# DISPLAY.net
KiCad netlist of a schematic drawn in EAGLE
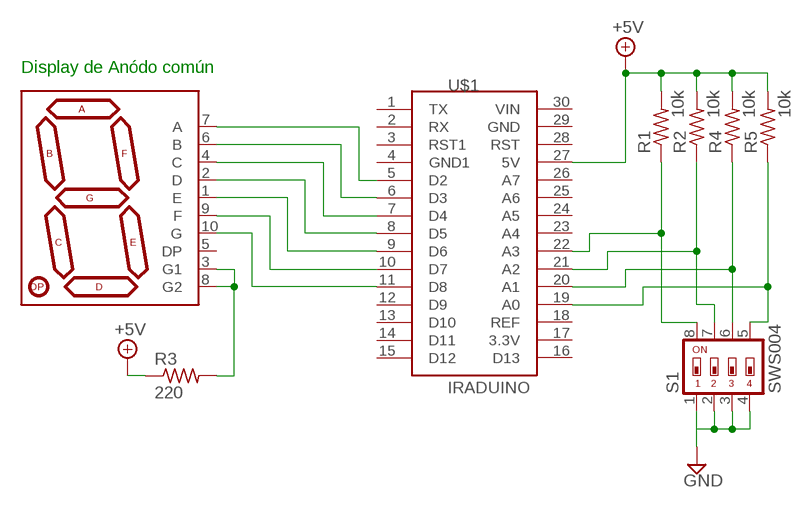
[diagram p0: schematic, sheet 1]

(export (version "E")
  (design (tool "Eeschema 10.0.6"))
  (components
    (comp (ref "R1")
      (value "10k")
      (footprint "eagle-import:0207_10")
      (libsource (lib "eagle-import") (part "R-US_0207/10"))
    )
    (comp (ref "R2")
      (value "10k")
      (footprint "eagle-import:0207_10")
      (libsource (lib "eagle-import") (part "R-US_0207/10"))
    )
    (comp (ref "R3")
      (value "220")
      (footprint "eagle-import:0207_10")
      (libsource (lib "eagle-import") (part "R-US_0207/10"))
    )
    (comp (ref "R4")
      (value "10k")
      (footprint "eagle-import:0207_10")
      (libsource (lib "eagle-import") (part "R-US_0207/10"))
    )
    (comp (ref "R5")
      (value "10k")
      (footprint "eagle-import:0207_10")
      (libsource (lib "eagle-import") (part "R-US_0207/10"))
    )
    (comp (ref "S1")
      (value "SWS004")
      (footprint "eagle-import:SMS-004")
      (libsource (lib "eagle-import") (part "SWS004"))
    )
    (comp (ref "U$1")
      (value "IRADUINO")
      (footprint "eagle-import:IRADUINO")
      (libsource (lib "eagle-import") (part "IRADUINO"))
    )
    (comp (ref "U$2")
      (value "7-SEGMENT-DISPLAYPTH")
      (footprint "eagle-import:7-SEGMENT-DISPLAY")
      (libsource (lib "eagle-import") (part "7-SEGMENT-DISPLAYPTH"))
    )
  )
  (nets
    (net (code "1") (name "+5V") (class "Default")
      (node (ref "R1") (pin "2") (pinfunction "2_2") (pintype "passive"))
      (node (ref "R2") (pin "2") (pinfunction "2_2") (pintype "passive"))
      (node (ref "R3") (pin "1") (pinfunction "1_1") (pintype "passive"))
      (node (ref "R4") (pin "2") (pinfunction "2_2") (pintype "passive"))
      (node (ref "R5") (pin "2") (pinfunction "2_2") (pintype "passive"))
      (node (ref "U$1") (pin "27") (pinfunction "5V_27") (pintype "bidirectional"))
    )
    (net (code "2") (name "GND") (class "Default")
      (node (ref "S1") (pin "1") (pinfunction "1_1") (pintype "passive"))
      (node (ref "S1") (pin "2") (pinfunction "2_2") (pintype "passive"))
      (node (ref "S1") (pin "3") (pinfunction "3_3") (pintype "passive"))
      (node (ref "S1") (pin "4") (pinfunction "4_4") (pintype "passive"))
    )
    (net (code "3") (name "Net-(U$1-A0)") (class "Default")
      (node (ref "R5") (pin "1") (pinfunction "1_1") (pintype "passive"))
      (node (ref "S1") (pin "5") (pinfunction "5_5") (pintype "passive"))
      (node (ref "U$1") (pin "19") (pinfunction "A0_19") (pintype "bidirectional"))
    )
    (net (code "4") (name "Net-(U$1-A1)") (class "Default")
      (node (ref "R4") (pin "1") (pinfunction "1_1") (pintype "passive"))
      (node (ref "S1") (pin "6") (pinfunction "6_6") (pintype "passive"))
      (node (ref "U$1") (pin "20") (pinfunction "A1_20") (pintype "bidirectional"))
    )
    (net (code "5") (name "Net-(U$1-A2)") (class "Default")
      (node (ref "R2") (pin "1") (pinfunction "1_1") (pintype "passive"))
      (node (ref "S1") (pin "7") (pinfunction "7_7") (pintype "passive"))
      (node (ref "U$1") (pin "21") (pinfunction "A2_21") (pintype "bidirectional"))
    )
    (net (code "6") (name "Net-(U$1-A3)") (class "Default")
      (node (ref "R1") (pin "1") (pinfunction "1_1") (pintype "passive"))
      (node (ref "S1") (pin "8") (pinfunction "8_8") (pintype "passive"))
      (node (ref "U$1") (pin "22") (pinfunction "A3_22") (pintype "bidirectional"))
    )
    (net (code "7") (name "Net-(U$1-D2)") (class "Default")
      (node (ref "U$1") (pin "5") (pinfunction "D2_5") (pintype "bidirectional"))
      (node (ref "U$2") (pin "7") (pinfunction "A_7") (pintype "bidirectional"))
    )
    (net (code "8") (name "Net-(U$1-D3)") (class "Default")
      (node (ref "U$1") (pin "6") (pinfunction "D3_6") (pintype "bidirectional"))
      (node (ref "U$2") (pin "6") (pinfunction "B_6") (pintype "bidirectional"))
    )
    (net (code "9") (name "Net-(U$1-D4)") (class "Default")
      (node (ref "U$1") (pin "7") (pinfunction "D4_7") (pintype "bidirectional"))
      (node (ref "U$2") (pin "4") (pinfunction "C_4") (pintype "bidirectional"))
    )
    (net (code "10") (name "Net-(U$1-D5)") (class "Default")
      (node (ref "U$1") (pin "8") (pinfunction "D5_8") (pintype "bidirectional"))
      (node (ref "U$2") (pin "2") (pinfunction "D_2") (pintype "bidirectional"))
    )
    (net (code "11") (name "Net-(U$1-D6)") (class "Default")
      (node (ref "U$1") (pin "9") (pinfunction "D6_9") (pintype "bidirectional"))
      (node (ref "U$2") (pin "1") (pinfunction "E_1") (pintype "bidirectional"))
    )
    (net (code "12") (name "Net-(U$1-D7)") (class "Default")
      (node (ref "U$1") (pin "10") (pinfunction "D7_10") (pintype "bidirectional"))
      (node (ref "U$2") (pin "9") (pinfunction "F_9") (pintype "bidirectional"))
    )
    (net (code "13") (name "Net-(U$1-D8)") (class "Default")
      (node (ref "U$1") (pin "11") (pinfunction "D8_11") (pintype "bidirectional"))
      (node (ref "U$2") (pin "10") (pinfunction "G_10") (pintype "bidirectional"))
    )
    (net (code "14") (name "Net-(U$2-G1)") (class "Default")
      (node (ref "R3") (pin "2") (pinfunction "2_2") (pintype "passive"))
      (node (ref "U$2") (pin "3") (pinfunction "G1_3") (pintype "bidirectional"))
      (node (ref "U$2") (pin "8") (pinfunction "G2_8") (pintype "bidirectional"))
    )
    (net (code "15") (name "unconnected-(U$1-3.3V-Pad17)") (class "Default")
      (node (ref "U$1") (pin "17") (pinfunction "3.3V_17") (pintype "bidirectional"))
    )
    (net (code "16") (name "unconnected-(U$1-A4-Pad23)") (class "Default")
      (node (ref "U$1") (pin "23") (pinfunction "A4_23") (pintype "bidirectional"))
    )
    (net (code "17") (name "unconnected-(U$1-A5-Pad24)") (class "Default")
      (node (ref "U$1") (pin "24") (pinfunction "A5_24") (pintype "bidirectional"))
    )
    (net (code "18") (name "unconnected-(U$1-A6-Pad25)") (class "Default")
      (node (ref "U$1") (pin "25") (pinfunction "A6_25") (pintype "bidirectional"))
    )
    (net (code "19") (name "unconnected-(U$1-A7-Pad26)") (class "Default")
      (node (ref "U$1") (pin "26") (pinfunction "A7_26") (pintype "bidirectional"))
    )
    (net (code "20") (name "unconnected-(U$1-D9-Pad12)") (class "Default")
      (node (ref "U$1") (pin "12") (pinfunction "D9_12") (pintype "bidirectional"))
    )
    (net (code "21") (name "unconnected-(U$1-D10-Pad13)") (class "Default")
      (node (ref "U$1") (pin "13") (pinfunction "D10_13") (pintype "bidirectional"))
    )
    (net (code "22") (name "unconnected-(U$1-D11-Pad14)") (class "Default")
      (node (ref "U$1") (pin "14") (pinfunction "D11_14") (pintype "bidirectional"))
    )
    (net (code "23") (name "unconnected-(U$1-D12-Pad15)") (class "Default")
      (node (ref "U$1") (pin "15") (pinfunction "D12_15") (pintype "bidirectional"))
    )
    (net (code "24") (name "unconnected-(U$1-D13-Pad16)") (class "Default")
      (node (ref "U$1") (pin "16") (pinfunction "D13_16") (pintype "bidirectional"))
    )
    (net (code "25") (name "unconnected-(U$1-GND-Pad29)") (class "Default")
      (node (ref "U$1") (pin "29") (pinfunction "GND_29") (pintype "bidirectional"))
    )
    (net (code "26") (name "unconnected-(U$1-GND1-Pad4)") (class "Default")
      (node (ref "U$1") (pin "4") (pinfunction "GND1_4") (pintype "bidirectional"))
    )
    (net (code "27") (name "unconnected-(U$1-REF-Pad18)") (class "Default")
      (node (ref "U$1") (pin "18") (pinfunction "REF_18") (pintype "bidirectional"))
    )
    (net (code "28") (name "unconnected-(U$1-RST-Pad28)") (class "Default")
      (node (ref "U$1") (pin "28") (pinfunction "RST_28") (pintype "bidirectional"))
    )
    (net (code "29") (name "unconnected-(U$1-RST1-Pad3)") (class "Default")
      (node (ref "U$1") (pin "3") (pinfunction "RST1_3") (pintype "bidirectional"))
    )
    (net (code "30") (name "unconnected-(U$1-RX-Pad2)") (class "Default")
      (node (ref "U$1") (pin "2") (pinfunction "RX_2") (pintype "bidirectional"))
    )
    (net (code "31") (name "unconnected-(U$1-TX-Pad1)") (class "Default")
      (node (ref "U$1") (pin "1") (pinfunction "TX_1") (pintype "bidirectional"))
    )
    (net (code "32") (name "unconnected-(U$1-VIN-Pad30)") (class "Default")
      (node (ref "U$1") (pin "30") (pinfunction "VIN_30") (pintype "bidirectional"))
    )
    (net (code "33") (name "unconnected-(U$2-DP-Pad5)") (class "Default")
      (node (ref "U$2") (pin "5") (pinfunction "DP_5") (pintype "bidirectional"))
    )
  )
)
